# 04_-_miniPCI.net
KiCad netlist of a schematic drawn in Altium Designer
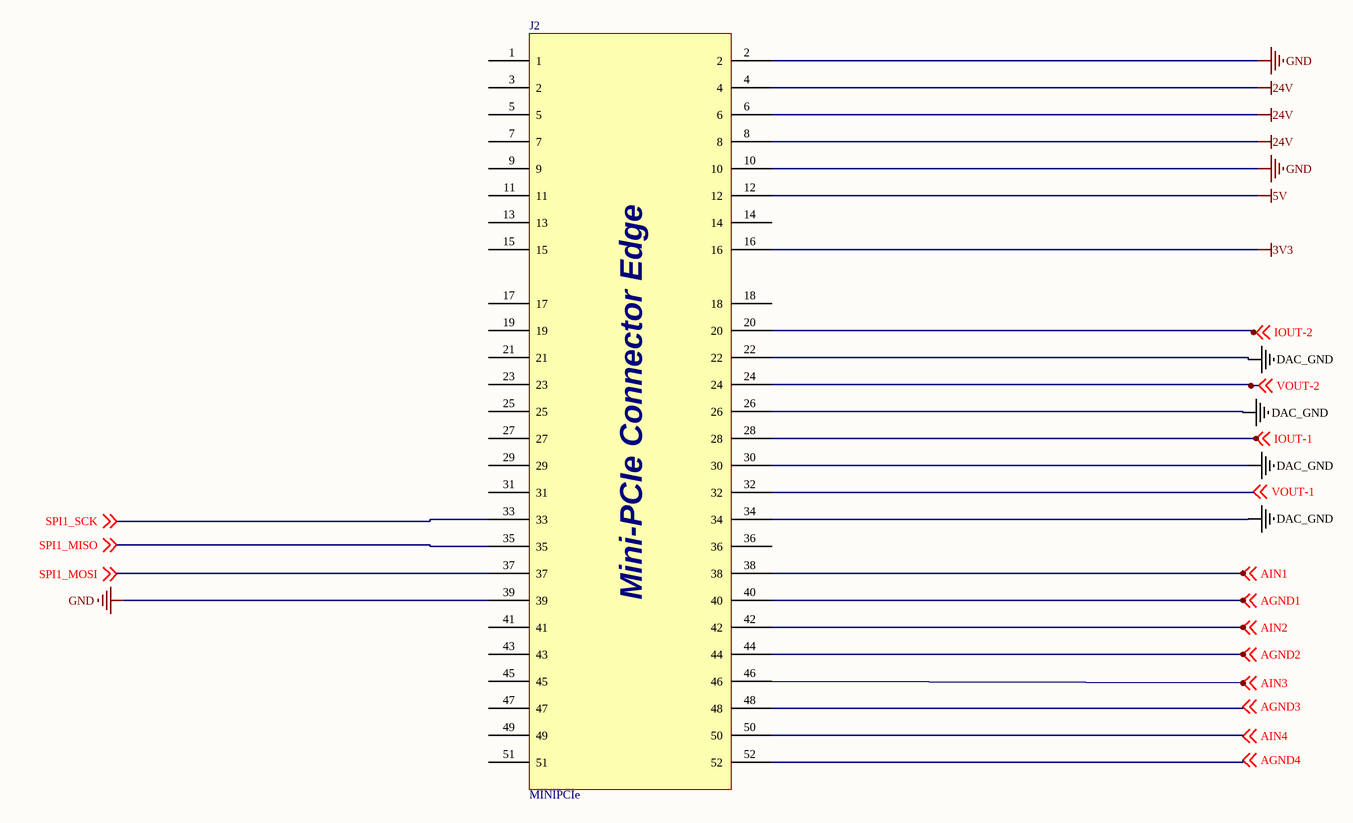
[diagram p0: [04] - miniPCI.SchDoc]

(export (version "E")
  (design (tool "Eeschema 10.0.6"))
  (components
    (comp (ref "J2")
      (value "MINIPCIe")
      (footprint "MINI PCIe")
      (libsource (lib "CPU_STM_080816") (part "MINIPCIe"))
    )
  )
  (nets
    (net (code "1") (name "3V3") (class "Default")
      (node (ref "J2") (pin "16") (pinfunction "16_16") (pintype "passive"))
    )
    (net (code "2") (name "5V") (class "Default")
      (node (ref "J2") (pin "12") (pinfunction "12_12") (pintype "passive"))
    )
    (net (code "3") (name "24V") (class "Default")
      (node (ref "J2") (pin "4") (pinfunction "4_4") (pintype "passive"))
      (node (ref "J2") (pin "6") (pinfunction "6_6") (pintype "passive"))
      (node (ref "J2") (pin "8") (pinfunction "8_8") (pintype "passive"))
    )
    (net (code "4") (name "AGND1") (class "Default")
      (node (ref "J2") (pin "40") (pinfunction "40_40") (pintype "passive"))
    )
    (net (code "5") (name "AGND2") (class "Default")
      (node (ref "J2") (pin "44") (pinfunction "44_44") (pintype "passive"))
    )
    (net (code "6") (name "AGND3") (class "Default")
      (node (ref "J2") (pin "48") (pinfunction "48_48") (pintype "passive"))
    )
    (net (code "7") (name "AGND4") (class "Default")
      (node (ref "J2") (pin "52") (pinfunction "52_52") (pintype "passive"))
    )
    (net (code "8") (name "AIN1") (class "Default")
      (node (ref "J2") (pin "38") (pinfunction "38_38") (pintype "passive"))
    )
    (net (code "9") (name "AIN2") (class "Default")
      (node (ref "J2") (pin "42") (pinfunction "42_42") (pintype "passive"))
    )
    (net (code "10") (name "AIN3") (class "Default")
      (node (ref "J2") (pin "46") (pinfunction "46_46") (pintype "passive"))
    )
    (net (code "11") (name "AIN4") (class "Default")
      (node (ref "J2") (pin "50") (pinfunction "50_50") (pintype "passive"))
    )
    (net (code "12") (name "DAC_GND") (class "Default")
      (node (ref "J2") (pin "22") (pinfunction "22_22") (pintype "passive"))
      (node (ref "J2") (pin "26") (pinfunction "26_26") (pintype "passive"))
      (node (ref "J2") (pin "30") (pinfunction "30_30") (pintype "passive"))
      (node (ref "J2") (pin "34") (pinfunction "34_34") (pintype "passive"))
    )
    (net (code "13") (name "GND") (class "Default")
      (node (ref "J2") (pin "10") (pinfunction "10_10") (pintype "passive"))
      (node (ref "J2") (pin "2") (pinfunction "2_2") (pintype "passive"))
      (node (ref "J2") (pin "39") (pinfunction "39_39") (pintype "passive"))
    )
    (net (code "14") (name "IOUT-1") (class "Default")
      (node (ref "J2") (pin "28") (pinfunction "28_28") (pintype "passive"))
    )
    (net (code "15") (name "IOUT-2") (class "Default")
      (node (ref "J2") (pin "20") (pinfunction "20_20") (pintype "passive"))
    )
    (net (code "16") (name "SPI1_MISO") (class "Default")
      (node (ref "J2") (pin "35") (pinfunction "35_35") (pintype "passive"))
    )
    (net (code "17") (name "SPI1_MOSI") (class "Default")
      (node (ref "J2") (pin "37") (pinfunction "37_37") (pintype "passive"))
    )
    (net (code "18") (name "SPI1_SCK") (class "Default")
      (node (ref "J2") (pin "33") (pinfunction "33_33") (pintype "passive"))
    )
    (net (code "19") (name "VOUT-1") (class "Default")
      (node (ref "J2") (pin "32") (pinfunction "32_32") (pintype "passive"))
    )
    (net (code "20") (name "VOUT-2") (class "Default")
      (node (ref "J2") (pin "24") (pinfunction "24_24") (pintype "passive"))
    )
    (net (code "21") (name "unconnected-(J2-2-Pad3)") (class "Default")
      (node (ref "J2") (pin "3") (pinfunction "2_3") (pintype "passive"))
    )
    (net (code "22") (name "unconnected-(J2-Pad1)") (class "Default")
      (node (ref "J2") (pin "1") (pinfunction "1_1") (pintype "passive"))
    )
    (net (code "23") (name "unconnected-(J2-Pad5)") (class "Default")
      (node (ref "J2") (pin "5") (pinfunction "5_5") (pintype "passive"))
    )
    (net (code "24") (name "unconnected-(J2-Pad7)") (class "Default")
      (node (ref "J2") (pin "7") (pinfunction "7_7") (pintype "passive"))
    )
    (net (code "25") (name "unconnected-(J2-Pad9)") (class "Default")
      (node (ref "J2") (pin "9") (pinfunction "9_9") (pintype "passive"))
    )
    (net (code "26") (name "unconnected-(J2-Pad11)") (class "Default")
      (node (ref "J2") (pin "11") (pinfunction "11_11") (pintype "passive"))
    )
    (net (code "27") (name "unconnected-(J2-Pad13)") (class "Default")
      (node (ref "J2") (pin "13") (pinfunction "13_13") (pintype "passive"))
    )
    (net (code "28") (name "unconnected-(J2-Pad14)") (class "Default")
      (node (ref "J2") (pin "14") (pinfunction "14_14") (pintype "passive"))
    )
    (net (code "29") (name "unconnected-(J2-Pad15)") (class "Default")
      (node (ref "J2") (pin "15") (pinfunction "15_15") (pintype "passive"))
    )
    (net (code "30") (name "unconnected-(J2-Pad17)") (class "Default")
      (node (ref "J2") (pin "17") (pinfunction "17_17") (pintype "passive"))
    )
    (net (code "31") (name "unconnected-(J2-Pad18)") (class "Default")
      (node (ref "J2") (pin "18") (pinfunction "18_18") (pintype "passive"))
    )
    (net (code "32") (name "unconnected-(J2-Pad19)") (class "Default")
      (node (ref "J2") (pin "19") (pinfunction "19_19") (pintype "passive"))
    )
    (net (code "33") (name "unconnected-(J2-Pad21)") (class "Default")
      (node (ref "J2") (pin "21") (pinfunction "21_21") (pintype "passive"))
    )
    (net (code "34") (name "unconnected-(J2-Pad23)") (class "Default")
      (node (ref "J2") (pin "23") (pinfunction "23_23") (pintype "passive"))
    )
    (net (code "35") (name "unconnected-(J2-Pad25)") (class "Default")
      (node (ref "J2") (pin "25") (pinfunction "25_25") (pintype "passive"))
    )
    (net (code "36") (name "unconnected-(J2-Pad27)") (class "Default")
      (node (ref "J2") (pin "27") (pinfunction "27_27") (pintype "passive"))
    )
    (net (code "37") (name "unconnected-(J2-Pad29)") (class "Default")
      (node (ref "J2") (pin "29") (pinfunction "29_29") (pintype "passive"))
    )
    (net (code "38") (name "unconnected-(J2-Pad31)") (class "Default")
      (node (ref "J2") (pin "31") (pinfunction "31_31") (pintype "passive"))
    )
    (net (code "39") (name "unconnected-(J2-Pad36)") (class "Default")
      (node (ref "J2") (pin "36") (pinfunction "36_36") (pintype "passive"))
    )
    (net (code "40") (name "unconnected-(J2-Pad41)") (class "Default")
      (node (ref "J2") (pin "41") (pinfunction "41_41") (pintype "passive"))
    )
    (net (code "41") (name "unconnected-(J2-Pad43)") (class "Default")
      (node (ref "J2") (pin "43") (pinfunction "43_43") (pintype "passive"))
    )
    (net (code "42") (name "unconnected-(J2-Pad45)") (class "Default")
      (node (ref "J2") (pin "45") (pinfunction "45_45") (pintype "passive"))
    )
    (net (code "43") (name "unconnected-(J2-Pad47)") (class "Default")
      (node (ref "J2") (pin "47") (pinfunction "47_47") (pintype "passive"))
    )
    (net (code "44") (name "unconnected-(J2-Pad49)") (class "Default")
      (node (ref "J2") (pin "49") (pinfunction "49_49") (pintype "passive"))
    )
    (net (code "45") (name "unconnected-(J2-Pad51)") (class "Default")
      (node (ref "J2") (pin "51") (pinfunction "51_51") (pintype "passive"))
    )
  )
)
